# transmitter_fm.net
KiCad netlist of a schematic drawn in EAGLE
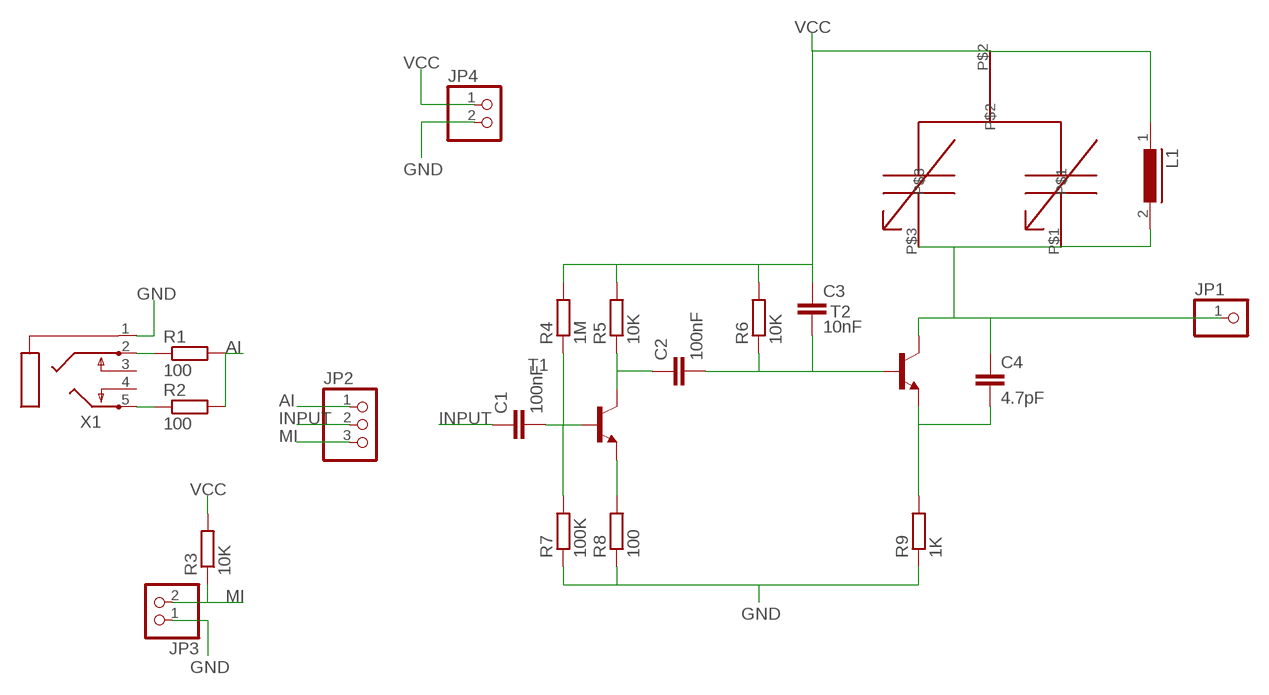
[diagram p0: schematic, sheet 1]

(export (version "E")
  (design (tool "Eeschema 10.0.6"))
  (components
    (comp (ref "C1")
      (value "100nF")
      (footprint "eagle-import:C050-035X075")
      (libsource (lib "eagle-import") (part "C-EU050-035X075"))
    )
    (comp (ref "C2")
      (value "100nF")
      (footprint "eagle-import:C050-035X075")
      (libsource (lib "eagle-import") (part "C-EU050-035X075"))
    )
    (comp (ref "C3")
      (value "10nF")
      (footprint "eagle-import:C050-035X075")
      (libsource (lib "eagle-import") (part "C-EU050-035X075"))
    )
    (comp (ref "C4")
      (value "4.7pF")
      (footprint "eagle-import:C025-025X050")
      (libsource (lib "eagle-import") (part "C-EU025-025X050"))
    )
    (comp (ref "JP1")
      (value "PINHD-1X1")
      (footprint "eagle-import:1X01")
      (libsource (lib "eagle-import") (part "PINHD-1X1"))
    )
    (comp (ref "JP2")
      (value "PINHD-1X3")
      (footprint "eagle-import:1X03")
      (libsource (lib "eagle-import") (part "PINHD-1X3"))
    )
    (comp (ref "JP3")
      (value "PINHD-1X2")
      (footprint "eagle-import:1X02")
      (libsource (lib "eagle-import") (part "PINHD-1X2"))
    )
    (comp (ref "JP4")
      (value "PINHD-1X2")
      (footprint "eagle-import:1X02")
      (libsource (lib "eagle-import") (part "PINHD-1X2"))
    )
    (comp (ref "L1")
      (value "DS10")
      (footprint "eagle-import:DS10")
      (libsource (lib "eagle-import") (part "DS10"))
    )
    (comp (ref "R1")
      (value "100")
      (footprint "eagle-import:0207_7")
      (libsource (lib "eagle-import") (part "R-EU_0207/7"))
    )
    (comp (ref "R2")
      (value "100")
      (footprint "eagle-import:0207_7")
      (libsource (lib "eagle-import") (part "R-EU_0207/7"))
    )
    (comp (ref "R3")
      (value "10K")
      (footprint "eagle-import:0207_7")
      (libsource (lib "eagle-import") (part "R-EU_0207/7"))
    )
    (comp (ref "R4")
      (value "1M")
      (footprint "eagle-import:0207_7")
      (libsource (lib "eagle-import") (part "R-EU_0207/7"))
    )
    (comp (ref "R5")
      (value "10K")
      (footprint "eagle-import:0207_7")
      (libsource (lib "eagle-import") (part "R-EU_0207/7"))
    )
    (comp (ref "R6")
      (value "10K")
      (footprint "eagle-import:0207_7")
      (libsource (lib "eagle-import") (part "R-EU_0207/7"))
    )
    (comp (ref "R7")
      (value "100K")
      (footprint "eagle-import:0207_7")
      (libsource (lib "eagle-import") (part "R-EU_0207/7"))
    )
    (comp (ref "R8")
      (value "100")
      (footprint "eagle-import:0207_7")
      (libsource (lib "eagle-import") (part "R-EU_0207/7"))
    )
    (comp (ref "R9")
      (value "1K")
      (footprint "eagle-import:0207_7")
      (libsource (lib "eagle-import") (part "R-EU_0207/7"))
    )
    (comp (ref "T1")
      (value "2N3904")
      (footprint "eagle-import:TO92")
      (libsource (lib "eagle-import") (part "2N3904"))
    )
    (comp (ref "T2")
      (value "2N3904")
      (footprint "eagle-import:TO92")
      (libsource (lib "eagle-import") (part "2N3904"))
    )
    (comp (ref "U$1")
      (value "VARCO_KEMATIAN_DEV")
      (footprint "eagle-import:VARCO_KEMATIAN")
      (libsource (lib "eagle-import") (part "VARCO_KEMATIAN_DEV"))
    )
    (comp (ref "X1")
      (value "PG203J")
      (footprint "eagle-import:PG203J")
      (libsource (lib "eagle-import") (part "PG203J"))
    )
  )
  (nets
    (net (code "1") (name "/AI") (class "Default")
      (node (ref "JP2") (pin "1") (pinfunction "1_1") (pintype "passive"))
      (node (ref "R1") (pin "2") (pinfunction "2_2") (pintype "passive"))
      (node (ref "R2") (pin "2") (pinfunction "2_2") (pintype "passive"))
    )
    (net (code "2") (name "/GND") (class "Default")
      (node (ref "JP3") (pin "1") (pinfunction "1_1") (pintype "passive"))
      (node (ref "JP4") (pin "2") (pinfunction "2_2") (pintype "passive"))
      (node (ref "R7") (pin "1") (pinfunction "1_1") (pintype "passive"))
      (node (ref "R8") (pin "1") (pinfunction "1_1") (pintype "passive"))
      (node (ref "R9") (pin "1") (pinfunction "1_1") (pintype "passive"))
      (node (ref "X1") (pin "1") (pinfunction "1_1") (pintype "passive"))
    )
    (net (code "3") (name "/INPUT") (class "Default")
      (node (ref "C1") (pin "1") (pinfunction "1_1") (pintype "passive"))
      (node (ref "JP2") (pin "2") (pinfunction "2_2") (pintype "passive"))
    )
    (net (code "4") (name "/MI") (class "Default")
      (node (ref "JP2") (pin "3") (pinfunction "3_3") (pintype "passive"))
      (node (ref "JP3") (pin "2") (pinfunction "2_2") (pintype "passive"))
      (node (ref "R3") (pin "1") (pinfunction "1_1") (pintype "passive"))
    )
    (net (code "5") (name "/VCC") (class "Default")
      (node (ref "C3") (pin "1") (pinfunction "1_1") (pintype "passive"))
      (node (ref "JP4") (pin "1") (pinfunction "1_1") (pintype "passive"))
      (node (ref "L1") (pin "1") (pinfunction "1_1") (pintype "passive"))
      (node (ref "R3") (pin "2") (pinfunction "2_2") (pintype "passive"))
      (node (ref "R4") (pin "2") (pinfunction "2_2") (pintype "passive"))
      (node (ref "R5") (pin "2") (pinfunction "2_2") (pintype "passive"))
      (node (ref "R6") (pin "2") (pinfunction "2_2") (pintype "passive"))
      (node (ref "U$1") (pin "P$2") (pinfunction "P$2_P$2") (pintype "bidirectional"))
    )
    (net (code "6") (name "Net-(R1-Pad1)") (class "Default")
      (node (ref "R1") (pin "1") (pinfunction "1_1") (pintype "passive"))
      (node (ref "X1") (pin "2") (pinfunction "2_2") (pintype "passive"))
    )
    (net (code "7") (name "Net-(R2-Pad1)") (class "Default")
      (node (ref "R2") (pin "1") (pinfunction "1_1") (pintype "passive"))
      (node (ref "X1") (pin "5") (pinfunction "5_5") (pintype "passive"))
    )
    (net (code "8") (name "Net-(T1-B)") (class "Default")
      (node (ref "C1") (pin "2") (pinfunction "2_2") (pintype "passive"))
      (node (ref "R4") (pin "1") (pinfunction "1_1") (pintype "passive"))
      (node (ref "R7") (pin "2") (pinfunction "2_2") (pintype "passive"))
      (node (ref "T1") (pin "2") (pinfunction "B_2") (pintype "passive"))
    )
    (net (code "9") (name "Net-(T1-C)") (class "Default")
      (node (ref "C2") (pin "1") (pinfunction "1_1") (pintype "passive"))
      (node (ref "R5") (pin "1") (pinfunction "1_1") (pintype "passive"))
      (node (ref "T1") (pin "1") (pinfunction "C_1") (pintype "passive"))
    )
    (net (code "10") (name "Net-(T1-E)") (class "Default")
      (node (ref "R8") (pin "2") (pinfunction "2_2") (pintype "passive"))
      (node (ref "T1") (pin "3") (pinfunction "E_3") (pintype "passive"))
    )
    (net (code "11") (name "Net-(T2-B)") (class "Default")
      (node (ref "C2") (pin "2") (pinfunction "2_2") (pintype "passive"))
      (node (ref "C3") (pin "2") (pinfunction "2_2") (pintype "passive"))
      (node (ref "R6") (pin "1") (pinfunction "1_1") (pintype "passive"))
      (node (ref "T2") (pin "2") (pinfunction "B_2") (pintype "passive"))
    )
    (net (code "12") (name "Net-(T2-C)") (class "Default")
      (node (ref "C4") (pin "1") (pinfunction "1_1") (pintype "passive"))
      (node (ref "JP1") (pin "1") (pinfunction "1_1") (pintype "passive"))
      (node (ref "L1") (pin "2") (pinfunction "2_2") (pintype "passive"))
      (node (ref "T2") (pin "1") (pinfunction "C_1") (pintype "passive"))
      (node (ref "U$1") (pin "P$1") (pinfunction "P$1_P$1") (pintype "bidirectional"))
      (node (ref "U$1") (pin "P$3") (pinfunction "P$3_P$3") (pintype "bidirectional"))
    )
    (net (code "13") (name "Net-(T2-E)") (class "Default")
      (node (ref "C4") (pin "2") (pinfunction "2_2") (pintype "passive"))
      (node (ref "R9") (pin "2") (pinfunction "2_2") (pintype "passive"))
      (node (ref "T2") (pin "3") (pinfunction "E_3") (pintype "passive"))
    )
    (net (code "14") (name "unconnected-(X1-Pad3)") (class "Default")
      (node (ref "X1") (pin "3") (pinfunction "3_3") (pintype "passive"))
    )
    (net (code "15") (name "unconnected-(X1-Pad4)") (class "Default")
      (node (ref "X1") (pin "4") (pinfunction "4_4") (pintype "passive"))
    )
  )
)
